# Motor_Connectors.net
KiCad netlist of a schematic drawn in Altium Designer
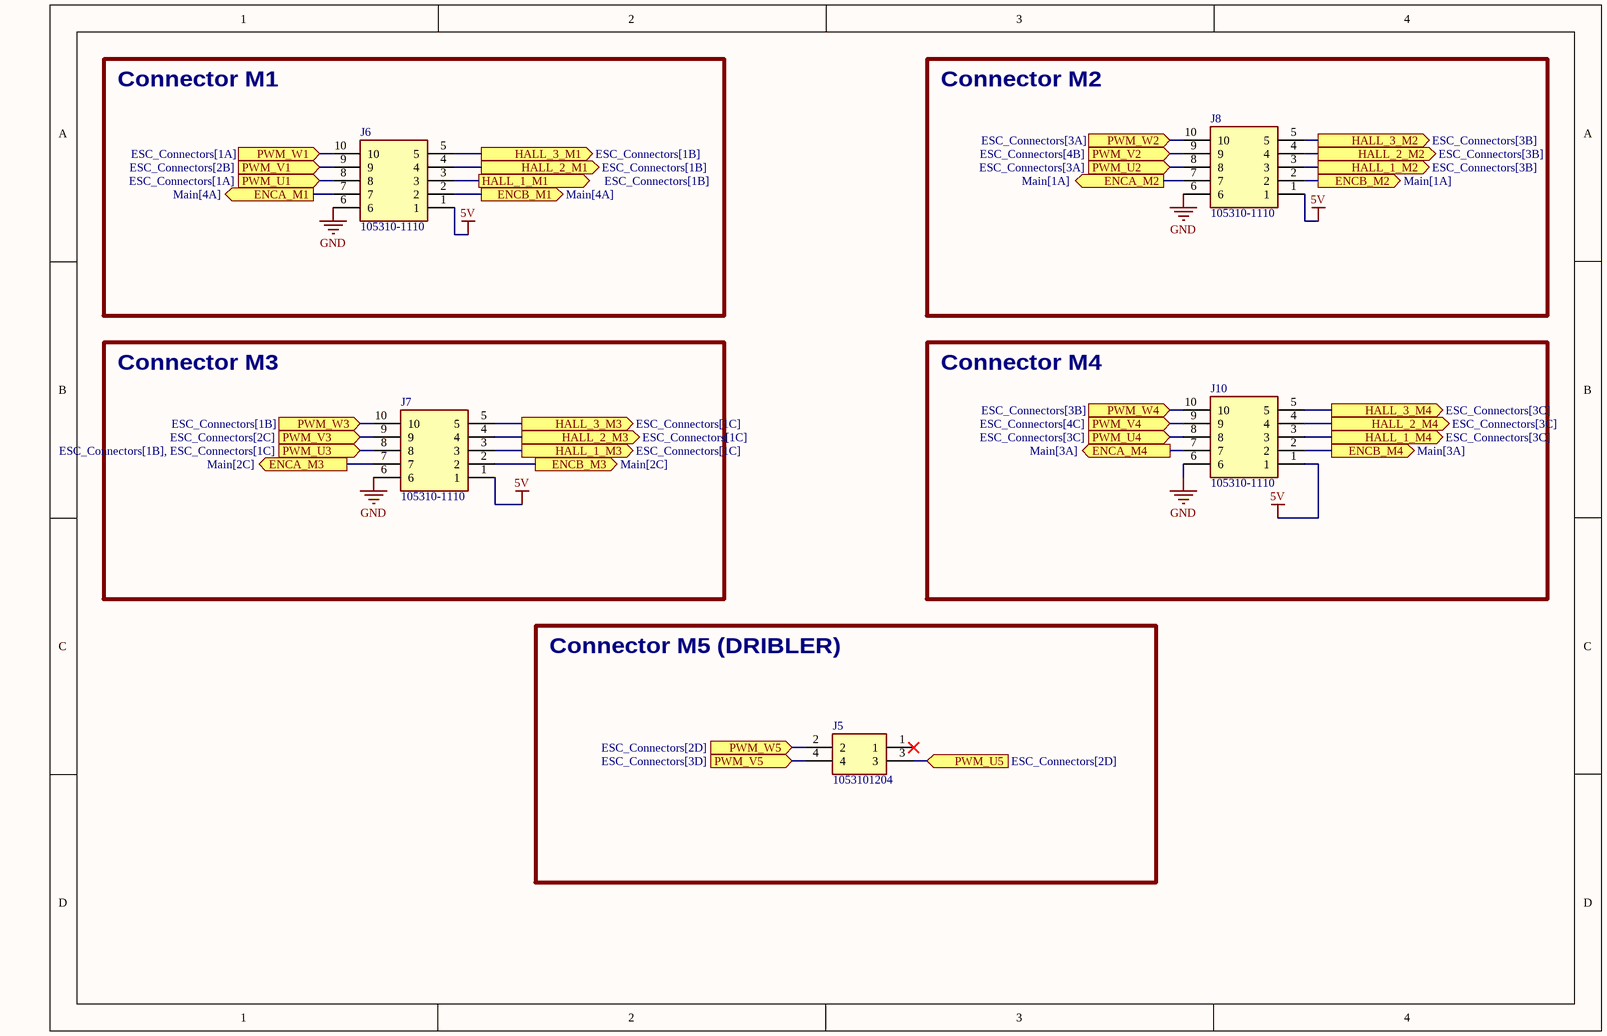
[diagram p0: Motor_Connectors.SchDoc]

(export (version "E")
  (design (tool "Eeschema 10.0.6"))
  (components
    (comp (ref "J5")
      (value "1053101204")
      (footprint "roboime:105310YY04_3")
      (description "Connector")
      (libsource (lib "roboime") (part "1053101204"))
    )
    (comp (ref "J6")
      (value "105310-1110")
      (footprint "roboime:1053101110")
      (description "Connector")
      (fields (field (name "MOUSER PART NUMBER") "538-105310-1110"))
      (libsource (lib "roboime") (part "105310-1110"))
    )
    (comp (ref "J7")
      (value "105310-1110")
      (footprint "roboime:1053101110")
      (description "Connector")
      (fields (field (name "MOUSER PART NUMBER") "538-105310-1110"))
      (libsource (lib "roboime") (part "105310-1110"))
    )
    (comp (ref "J8")
      (value "105310-1110")
      (footprint "roboime:1053101110")
      (description "Connector")
      (fields (field (name "MOUSER PART NUMBER") "538-105310-1110"))
      (libsource (lib "roboime") (part "105310-1110"))
    )
    (comp (ref "J10")
      (value "105310-1110")
      (footprint "roboime:1053101110")
      (description "Connector")
      (fields (field (name "MOUSER PART NUMBER") "538-105310-1110"))
      (libsource (lib "roboime") (part "105310-1110"))
    )
  )
  (nets
    (net (code "1") (name "/ENCA_M1") (class "Default")
      (node (ref "J6") (pin "7") (pinfunction "7_7") (pintype "passive"))
    )
    (net (code "2") (name "/ENCA_M2") (class "Default")
      (node (ref "J8") (pin "7") (pinfunction "7_7") (pintype "passive"))
    )
    (net (code "3") (name "/ENCA_M3") (class "Default")
      (node (ref "J7") (pin "7") (pinfunction "7_7") (pintype "passive"))
    )
    (net (code "4") (name "/ENCA_M4") (class "Default")
      (node (ref "J10") (pin "7") (pinfunction "7_7") (pintype "passive"))
    )
    (net (code "5") (name "/ENCB_M1") (class "Default")
      (node (ref "J6") (pin "2") (pinfunction "2_2") (pintype "passive"))
    )
    (net (code "6") (name "/ENCB_M2") (class "Default")
      (node (ref "J8") (pin "2") (pinfunction "2_2") (pintype "passive"))
    )
    (net (code "7") (name "/ENCB_M3") (class "Default")
      (node (ref "J7") (pin "2") (pinfunction "2_2") (pintype "passive"))
    )
    (net (code "8") (name "/ENCB_M4") (class "Default")
      (node (ref "J10") (pin "2") (pinfunction "2_2") (pintype "passive"))
    )
    (net (code "9") (name "/HALL_1_M1") (class "Default")
      (node (ref "J6") (pin "3") (pinfunction "3_3") (pintype "passive"))
    )
    (net (code "10") (name "/HALL_1_M2") (class "Default")
      (node (ref "J8") (pin "3") (pinfunction "3_3") (pintype "passive"))
    )
    (net (code "11") (name "/HALL_1_M3") (class "Default")
      (node (ref "J7") (pin "3") (pinfunction "3_3") (pintype "passive"))
    )
    (net (code "12") (name "/HALL_1_M4") (class "Default")
      (node (ref "J10") (pin "3") (pinfunction "3_3") (pintype "passive"))
    )
    (net (code "13") (name "/HALL_2_M1") (class "Default")
      (node (ref "J6") (pin "4") (pinfunction "4_4") (pintype "passive"))
    )
    (net (code "14") (name "/HALL_2_M2") (class "Default")
      (node (ref "J8") (pin "4") (pinfunction "4_4") (pintype "passive"))
    )
    (net (code "15") (name "/HALL_2_M3") (class "Default")
      (node (ref "J7") (pin "4") (pinfunction "4_4") (pintype "passive"))
    )
    (net (code "16") (name "/HALL_2_M4") (class "Default")
      (node (ref "J10") (pin "4") (pinfunction "4_4") (pintype "passive"))
    )
    (net (code "17") (name "/HALL_3_M1") (class "Default")
      (node (ref "J6") (pin "5") (pinfunction "5_5") (pintype "passive"))
    )
    (net (code "18") (name "/HALL_3_M2") (class "Default")
      (node (ref "J8") (pin "5") (pinfunction "5_5") (pintype "passive"))
    )
    (net (code "19") (name "/HALL_3_M3") (class "Default")
      (node (ref "J7") (pin "5") (pinfunction "5_5") (pintype "passive"))
    )
    (net (code "20") (name "/HALL_3_M4") (class "Default")
      (node (ref "J10") (pin "5") (pinfunction "5_5") (pintype "passive"))
    )
    (net (code "21") (name "/PWM_U1") (class "Default")
      (node (ref "J6") (pin "8") (pinfunction "8_8") (pintype "passive"))
    )
    (net (code "22") (name "/PWM_U2") (class "Default")
      (node (ref "J8") (pin "8") (pinfunction "8_8") (pintype "passive"))
    )
    (net (code "23") (name "/PWM_U3") (class "Default")
      (node (ref "J7") (pin "8") (pinfunction "8_8") (pintype "passive"))
    )
    (net (code "24") (name "/PWM_U4") (class "Default")
      (node (ref "J10") (pin "8") (pinfunction "8_8") (pintype "passive"))
    )
    (net (code "25") (name "/PWM_U5") (class "Default")
      (node (ref "J5") (pin "3") (pinfunction "3_3") (pintype "passive"))
    )
    (net (code "26") (name "/PWM_V1") (class "Default")
      (node (ref "J6") (pin "9") (pinfunction "9_9") (pintype "passive"))
    )
    (net (code "27") (name "/PWM_V2") (class "Default")
      (node (ref "J8") (pin "9") (pinfunction "9_9") (pintype "passive"))
    )
    (net (code "28") (name "/PWM_V3") (class "Default")
      (node (ref "J7") (pin "9") (pinfunction "9_9") (pintype "passive"))
    )
    (net (code "29") (name "/PWM_V4") (class "Default")
      (node (ref "J10") (pin "9") (pinfunction "9_9") (pintype "passive"))
    )
    (net (code "30") (name "/PWM_V5") (class "Default")
      (node (ref "J5") (pin "4") (pinfunction "4_4") (pintype "passive"))
    )
    (net (code "31") (name "/PWM_W1") (class "Default")
      (node (ref "J6") (pin "10") (pinfunction "10_10") (pintype "passive"))
    )
    (net (code "32") (name "/PWM_W2") (class "Default")
      (node (ref "J8") (pin "10") (pinfunction "10_10") (pintype "passive"))
    )
    (net (code "33") (name "/PWM_W3") (class "Default")
      (node (ref "J7") (pin "10") (pinfunction "10_10") (pintype "passive"))
    )
    (net (code "34") (name "/PWM_W4") (class "Default")
      (node (ref "J10") (pin "10") (pinfunction "10_10") (pintype "passive"))
    )
    (net (code "35") (name "/PWM_W5") (class "Default")
      (node (ref "J5") (pin "2") (pinfunction "2_2") (pintype "passive"))
    )
    (net (code "36") (name "5V") (class "Default")
      (node (ref "J10") (pin "1") (pinfunction "1_1") (pintype "passive"))
      (node (ref "J6") (pin "1") (pinfunction "1_1") (pintype "passive"))
      (node (ref "J7") (pin "1") (pinfunction "1_1") (pintype "passive"))
      (node (ref "J8") (pin "1") (pinfunction "1_1") (pintype "passive"))
    )
    (net (code "37") (name "GND") (class "Default")
      (node (ref "J10") (pin "6") (pinfunction "6_6") (pintype "passive"))
      (node (ref "J6") (pin "6") (pinfunction "6_6") (pintype "passive"))
      (node (ref "J7") (pin "6") (pinfunction "6_6") (pintype "passive"))
      (node (ref "J8") (pin "6") (pinfunction "6_6") (pintype "passive"))
    )
    (net (code "38") (name "unconnected-(J5-Pad1)") (class "Default")
      (node (ref "J5") (pin "1") (pinfunction "1_1") (pintype "passive+no_connect"))
    )
  )
)
